# GNSS_FE.net
KiCad netlist of a schematic drawn in Altium Designer
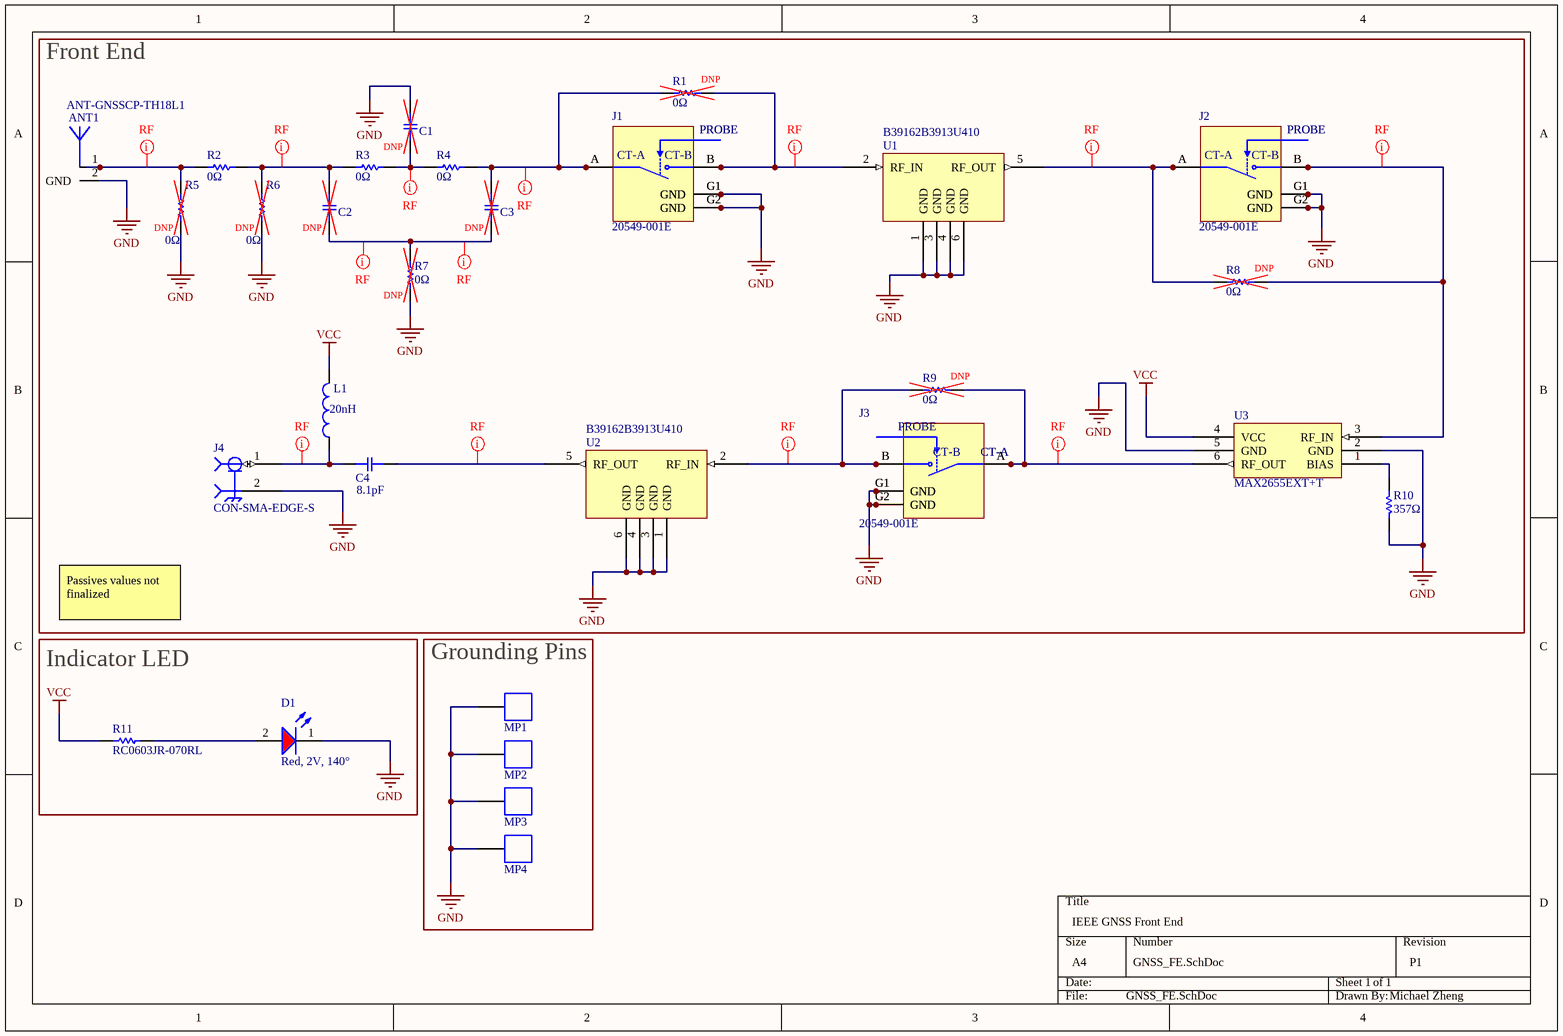
[diagram p0: GNSS_FE.SchDoc]

(export (version "E")
  (design (tool "Eeschema 10.0.6"))
  (components
    (comp (ref "ANT1")
      (value "ANT-GNSSCP-TH18L1")
      (footprint "ANT-GNSSCP-TH18L1")
      (description "CERAMIC PATCH GNSS ANTENNA")
      (libsource (lib "Symbols") (part "ANT-GNSSCP-TH18L1"))
    )
    (comp (ref "C1")
      (value "GRM188R61A105KA61D")
      (footprint "CAP_MURATA_0603")
      (description "CAP CER 1UF 10V X5R 0603")
      (libsource (lib "Symbols") (part "GRM188R61A105KA61D"))
    )
    (comp (ref "C2")
      (value "GRM188R61A105KA61D")
      (footprint "CAP_MURATA_0603")
      (description "CAP CER 1UF 10V X5R 0603")
      (libsource (lib "Symbols") (part "GRM188R61A105KA61D"))
    )
    (comp (ref "C3")
      (value "GRM188R61A105KA61D")
      (footprint "CAP_MURATA_0603")
      (description "CAP CER 1UF 10V X5R 0603")
      (libsource (lib "Symbols") (part "GRM188R61A105KA61D"))
    )
    (comp (ref "C4")
      (value "GRM188R61A105KA61D")
      (footprint "CAP_MURATA_0603")
      (description "CAP CER 1UF 10V X5R 0603")
      (fields (field (name "CAPACITANCE") "8.1pF"))
      (libsource (lib "Symbols") (part "GRM188R61A105KA61D"))
    )
    (comp (ref "D1")
      (value "Red, 2V, 140°")
      (footprint "WL-SMCW")
      (description "WL-SMCW Mono-color Chip LED Waterclear, SMT, size 0603, Red, 2V, 140°")
      (fields
        (field (name "MANUFACTURER PART NUMBER") "150060RS75000")
        (field (name "MANUFACTURER") "Wurth Elektronik")
      )
      (libsource (lib "Symbols") (part "150060RS75000"))
    )
    (comp (ref "J1")
      (value "20549-001E")
      (footprint "footprints:IPEX_20549-001E")
      (fields (field (name "MF") "I-PEX"))
      (libsource (lib "Symbols") (part "20549-001E"))
    )
    (comp (ref "J2")
      (value "20549-001E")
      (footprint "footprints:IPEX_20549-001E")
      (fields (field (name "MF") "I-PEX"))
      (libsource (lib "Symbols") (part "20549-001E"))
    )
    (comp (ref "J3")
      (value "20549-001E")
      (footprint "footprints:IPEX_20549-001E")
      (fields (field (name "MF") "I-PEX"))
      (libsource (lib "") (part "20549-001E_1"))
    )
    (comp (ref "J4")
      (value "CON-SMA-EDGE-S")
      (footprint "RFSOLUTIONS_CON-SMA-EDGE-S")
      (description "CONN SMA JACK STR EDGE MNT")
      (libsource (lib "Symbols") (part "CON-SMA-EDGE-S"))
    )
    (comp (ref "L1")
      (value "20nH")
      (footprint "INDC1006X60N")
      (description "FIXED IND 3.6NH 900MA 40 MOHM")
      (fields (field (name "MP") "LQW15AN3N6C10D"))
      (libsource (lib "Symbols") (part "LQW15AN3N6C10D"))
    )
    (comp (ref "MP1")
      (value "36900000")
      (footprint "36900000")
      (description "WE-SHC Shielding Cabinet, Clip, Tin Plated, Tape and Reel, 6.5x0.8x1.27mm")
      (fields (field (name "MANUFACTURER") "Wurth Elektronik"))
      (libsource (lib "Symbols") (part "36900000"))
    )
    (comp (ref "MP2")
      (value "36900000")
      (footprint "36900000")
      (description "WE-SHC Shielding Cabinet, Clip, Tin Plated, Tape and Reel, 6.5x0.8x1.27mm")
      (fields (field (name "MANUFACTURER") "Wurth Elektronik"))
      (libsource (lib "Symbols") (part "36900000"))
    )
    (comp (ref "MP3")
      (value "36900000")
      (footprint "36900000")
      (description "WE-SHC Shielding Cabinet, Clip, Tin Plated, Tape and Reel, 6.5x0.8x1.27mm")
      (fields (field (name "MANUFACTURER") "Wurth Elektronik"))
      (libsource (lib "Symbols") (part "36900000"))
    )
    (comp (ref "MP4")
      (value "36900000")
      (footprint "36900000")
      (description "WE-SHC Shielding Cabinet, Clip, Tin Plated, Tape and Reel, 6.5x0.8x1.27mm")
      (fields (field (name "MANUFACTURER") "Wurth Elektronik"))
      (libsource (lib "Symbols") (part "36900000"))
    )
    (comp (ref "R1")
      (value "RC0603JR-070RL")
      (footprint "RC0603JR-070RL")
      (description "Chip Resistor, 0 Ohm, +/- 5%, 0.1 W, -55 to 155 degC, 0603 (1608 Metric), RoHS, Tape and Reel")
      (fields
        (field (name "TOLERANCE") "5%")
        (field (name "RESISTANCE") "0Ω")
        (field (name "MANUFACTURER") "Yageo")
      )
      (libsource (lib "Symbols") (part "RC0603JR-070RL"))
    )
    (comp (ref "R2")
      (value "RC0603JR-070RL")
      (footprint "RC0603JR-070RL")
      (description "Chip Resistor, 0 Ohm, +/- 5%, 0.1 W, -55 to 155 degC, 0603 (1608 Metric), RoHS, Tape and Reel")
      (fields
        (field (name "TOLERANCE") "5%")
        (field (name "RESISTANCE") "0Ω")
        (field (name "MANUFACTURER") "Yageo")
      )
      (libsource (lib "Symbols") (part "RC0603JR-070RL"))
    )
    (comp (ref "R3")
      (value "RC0603JR-070RL")
      (footprint "RC0603JR-070RL")
      (description "Chip Resistor, 0 Ohm, +/- 5%, 0.1 W, -55 to 155 degC, 0603 (1608 Metric), RoHS, Tape and Reel")
      (fields
        (field (name "TOLERANCE") "5%")
        (field (name "RESISTANCE") "0Ω")
        (field (name "MANUFACTURER") "Yageo")
      )
      (libsource (lib "Symbols") (part "RC0603JR-070RL"))
    )
    (comp (ref "R4")
      (value "RC0603JR-070RL")
      (footprint "RC0603JR-070RL")
      (description "Chip Resistor, 0 Ohm, +/- 5%, 0.1 W, -55 to 155 degC, 0603 (1608 Metric), RoHS, Tape and Reel")
      (fields
        (field (name "TOLERANCE") "5%")
        (field (name "RESISTANCE") "0Ω")
        (field (name "MANUFACTURER") "Yageo")
      )
      (libsource (lib "Symbols") (part "RC0603JR-070RL"))
    )
    (comp (ref "R5")
      (value "RC0603JR-070RL")
      (footprint "RC0603JR-070RL")
      (description "Chip Resistor, 0 Ohm, +/- 5%, 0.1 W, -55 to 155 degC, 0603 (1608 Metric), RoHS, Tape and Reel")
      (fields
        (field (name "TOLERANCE") "5%")
        (field (name "RESISTANCE") "0Ω")
        (field (name "MANUFACTURER") "Yageo")
      )
      (libsource (lib "Symbols") (part "RC0603JR-070RL"))
    )
    (comp (ref "R6")
      (value "RC0603JR-070RL")
      (footprint "RC0603JR-070RL")
      (description "Chip Resistor, 0 Ohm, +/- 5%, 0.1 W, -55 to 155 degC, 0603 (1608 Metric), RoHS, Tape and Reel")
      (fields
        (field (name "TOLERANCE") "5%")
        (field (name "RESISTANCE") "0Ω")
        (field (name "MANUFACTURER") "Yageo")
      )
      (libsource (lib "Symbols") (part "RC0603JR-070RL"))
    )
    (comp (ref "R7")
      (value "RC0603JR-070RL")
      (footprint "RC0603JR-070RL")
      (description "Chip Resistor, 0 Ohm, +/- 5%, 0.1 W, -55 to 155 degC, 0603 (1608 Metric), RoHS, Tape and Reel")
      (fields
        (field (name "TOLERANCE") "5%")
        (field (name "RESISTANCE") "0Ω")
        (field (name "MANUFACTURER") "Yageo")
      )
      (libsource (lib "Symbols") (part "RC0603JR-070RL"))
    )
    (comp (ref "R8")
      (value "RC0603JR-070RL")
      (footprint "RC0603JR-070RL")
      (description "Chip Resistor, 0 Ohm, +/- 5%, 0.1 W, -55 to 155 degC, 0603 (1608 Metric), RoHS, Tape and Reel")
      (fields
        (field (name "TOLERANCE") "5%")
        (field (name "RESISTANCE") "0Ω")
        (field (name "MANUFACTURER") "Yageo")
      )
      (libsource (lib "Symbols") (part "RC0603JR-070RL"))
    )
    (comp (ref "R9")
      (value "RC0603JR-070RL")
      (footprint "RC0603JR-070RL")
      (description "Chip Resistor, 0 Ohm, +/- 5%, 0.1 W, -55 to 155 degC, 0603 (1608 Metric), RoHS, Tape and Reel")
      (fields
        (field (name "TOLERANCE") "5%")
        (field (name "RESISTANCE") "0Ω")
        (field (name "MANUFACTURER") "Yageo")
      )
      (libsource (lib "Symbols") (part "RC0603JR-070RL"))
    )
    (comp (ref "R10")
      (value "~")
      (footprint "RC0603JR-070RL")
      (description "Chip Resistor, 0 Ohm, +/- 5%, 0.1 W, -55 to 155 degC, 0603 (1608 Metric), RoHS, Tape and Reel")
      (fields
        (field (name "TOLERANCE") "5%")
        (field (name "RESISTANCE") "357Ω")
        (field (name "MANUFACTURER") "Yageo")
      )
      (libsource (lib "Symbols") (part "RC0603JR-070RL"))
    )
    (comp (ref "R11")
      (value "RC0603JR-070RL")
      (footprint "RC0603JR-070RL")
      (description "Chip Resistor, 0 Ohm, +/- 5%, 0.1 W, -55 to 155 degC, 0603 (1608 Metric), RoHS, Tape and Reel")
      (fields (field (name "TOLERANCE") "5%") (field (name "MANUFACTURER") "Yageo"))
      (libsource (lib "Symbols") (part "RC0603JR-070RL"))
    )
    (comp (ref "U1")
      (value "B39162B3913U410")
      (footprint "B39162B3913U410")
      (description "FILTER SAW 1.588GHZ 6SMD")
      (libsource (lib "Symbols") (part "B39162B3913U410"))
    )
    (comp (ref "U2")
      (value "B39162B3913U410")
      (footprint "B39162B3913U410")
      (description "FILTER SAW 1.588GHZ 6SMD")
      (libsource (lib "") (part "B39162B3913U410_1"))
    )
    (comp (ref "U3")
      (value "MAX2655EXT+T")
      (footprint "MAX2655EXT+T")
      (description "IC AMP GPS 1.4GHZ-1.7GHZ SC70-6")
      (libsource (lib "Symbols") (part "MAX2655EXT+T"))
    )
  )
  (nets
    (net (code "1") (name "GND") (class "Default")
      (node (ref "ANT1") (pin "2") (pinfunction "GND_2") (pintype "passive"))
      (node (ref "C1") (pin "2") (pinfunction "2_2") (pintype "passive"))
      (node (ref "D1") (pin "1") (pinfunction "K_1") (pintype "passive"))
      (node (ref "J1") (pin "G1") (pinfunction "GND_G1") (pintype "power_in"))
      (node (ref "J1") (pin "G2") (pinfunction "GND_G2") (pintype "power_in"))
      (node (ref "J2") (pin "G1") (pinfunction "GND_G1") (pintype "power_in"))
      (node (ref "J2") (pin "G2") (pinfunction "GND_G2") (pintype "power_in"))
      (node (ref "J3") (pin "G1") (pinfunction "GND_G1") (pintype "power_in"))
      (node (ref "J3") (pin "G2") (pinfunction "GND_G2") (pintype "power_in"))
      (node (ref "J4") (pin "2") (pinfunction "GND_2") (pintype "power_in"))
      (node (ref "MP1") (pin "1") (pinfunction "1_1") (pintype "passive"))
      (node (ref "MP2") (pin "1") (pinfunction "1_1") (pintype "passive"))
      (node (ref "MP3") (pin "1") (pinfunction "1_1") (pintype "passive"))
      (node (ref "MP4") (pin "1") (pinfunction "1_1") (pintype "passive"))
      (node (ref "R10") (pin "2") (pinfunction "2_2") (pintype "passive"))
      (node (ref "R5") (pin "1") (pinfunction "1_1") (pintype "passive"))
      (node (ref "R6") (pin "1") (pinfunction "1_1") (pintype "passive"))
      (node (ref "R7") (pin "2") (pinfunction "2_2") (pintype "passive"))
      (node (ref "U1") (pin "1") (pinfunction "GND_1") (pintype "power_in"))
      (node (ref "U1") (pin "3") (pinfunction "GND_3") (pintype "power_in"))
      (node (ref "U1") (pin "4") (pinfunction "GND_4") (pintype "power_in"))
      (node (ref "U1") (pin "6") (pinfunction "GND_6") (pintype "power_in"))
      (node (ref "U2") (pin "1") (pinfunction "GND_1") (pintype "power_in"))
      (node (ref "U2") (pin "3") (pinfunction "GND_3") (pintype "power_in"))
      (node (ref "U2") (pin "4") (pinfunction "GND_4") (pintype "power_in"))
      (node (ref "U2") (pin "6") (pinfunction "GND_6") (pintype "power_in"))
      (node (ref "U3") (pin "2") (pinfunction "GND_2") (pintype "power_in"))
      (node (ref "U3") (pin "5") (pinfunction "GND_5") (pintype "power_in"))
    )
    (net (code "2") (name "Net-(ANT1-RF_IN)") (class "Default")
      (node (ref "ANT1") (pin "1") (pinfunction "RF_IN_1") (pintype "passive"))
      (node (ref "R2") (pin "2") (pinfunction "2_2") (pintype "passive"))
      (node (ref "R5") (pin "2") (pinfunction "2_2") (pintype "passive"))
    )
    (net (code "3") (name "Net-(C1-Pad1)") (class "Default")
      (node (ref "C1") (pin "1") (pinfunction "1_1") (pintype "passive"))
      (node (ref "R3") (pin "1") (pinfunction "1_1") (pintype "passive"))
      (node (ref "R4") (pin "2") (pinfunction "2_2") (pintype "passive"))
    )
    (net (code "4") (name "Net-(C2-Pad1)") (class "Default")
      (node (ref "C2") (pin "1") (pinfunction "1_1") (pintype "passive"))
      (node (ref "C3") (pin "1") (pinfunction "1_1") (pintype "passive"))
      (node (ref "R7") (pin "1") (pinfunction "1_1") (pintype "passive"))
    )
    (net (code "5") (name "Net-(C2-Pad2)") (class "Default")
      (node (ref "C2") (pin "2") (pinfunction "2_2") (pintype "passive"))
      (node (ref "R2") (pin "1") (pinfunction "1_1") (pintype "passive"))
      (node (ref "R3") (pin "2") (pinfunction "2_2") (pintype "passive"))
      (node (ref "R6") (pin "2") (pinfunction "2_2") (pintype "passive"))
    )
    (net (code "6") (name "Net-(D1-A)") (class "Default")
      (node (ref "D1") (pin "2") (pinfunction "A_2") (pintype "passive"))
      (node (ref "R11") (pin "2") (pinfunction "2_2") (pintype "passive"))
    )
    (net (code "7") (name "Net-(J1-CT-A)") (class "Default")
      (node (ref "C3") (pin "2") (pinfunction "2_2") (pintype "passive"))
      (node (ref "J1") (pin "A") (pinfunction "CT-A_A") (pintype "passive"))
      (node (ref "R1") (pin "2") (pinfunction "2_2") (pintype "passive"))
      (node (ref "R4") (pin "1") (pinfunction "1_1") (pintype "passive"))
    )
    (net (code "8") (name "Net-(J1-CT-B)") (class "Default")
      (node (ref "J1") (pin "B") (pinfunction "CT-B_B") (pintype "passive"))
      (node (ref "R1") (pin "1") (pinfunction "1_1") (pintype "passive"))
      (node (ref "U1") (pin "2") (pinfunction "RF_IN_2") (pintype "input"))
    )
    (net (code "9") (name "Net-(J2-CT-A)") (class "Default")
      (node (ref "J2") (pin "A") (pinfunction "CT-A_A") (pintype "passive"))
      (node (ref "R8") (pin "2") (pinfunction "2_2") (pintype "passive"))
      (node (ref "U1") (pin "5") (pinfunction "RF_OUT_5") (pintype "output"))
    )
    (net (code "10") (name "Net-(J2-CT-B)") (class "Default")
      (node (ref "J2") (pin "B") (pinfunction "CT-B_B") (pintype "passive"))
      (node (ref "R8") (pin "1") (pinfunction "1_1") (pintype "passive"))
      (node (ref "U3") (pin "3") (pinfunction "RF_IN_3") (pintype "input"))
    )
    (net (code "11") (name "Net-(J3-CT-A)") (class "Default")
      (node (ref "J3") (pin "A") (pinfunction "CT-A_A") (pintype "passive"))
      (node (ref "R9") (pin "2") (pinfunction "2_2") (pintype "passive"))
      (node (ref "U3") (pin "6") (pinfunction "RF_OUT_6") (pintype "output"))
    )
    (net (code "12") (name "Net-(J3-CT-B)") (class "Default")
      (node (ref "J3") (pin "B") (pinfunction "CT-B_B") (pintype "passive"))
      (node (ref "R9") (pin "1") (pinfunction "1_1") (pintype "passive"))
      (node (ref "U2") (pin "2") (pinfunction "RF_IN_2") (pintype "input"))
    )
    (net (code "13") (name "Net-(J4-RF)") (class "Default")
      (node (ref "C4") (pin "2") (pinfunction "2_2") (pintype "passive"))
      (node (ref "J4") (pin "1") (pinfunction "RF_1") (pintype "bidirectional"))
      (node (ref "L1") (pin "1") (pinfunction "1_1") (pintype "passive"))
    )
    (net (code "14") (name "Net-(U2-RF_OUT)") (class "Default")
      (node (ref "C4") (pin "1") (pinfunction "1_1") (pintype "passive"))
      (node (ref "U2") (pin "5") (pinfunction "RF_OUT_5") (pintype "output"))
    )
    (net (code "15") (name "Net-(U3-BIAS)") (class "Default")
      (node (ref "R10") (pin "1") (pinfunction "1_1") (pintype "passive"))
      (node (ref "U3") (pin "1") (pinfunction "BIAS_1") (pintype "passive"))
    )
    (net (code "16") (name "VCC") (class "Default")
      (node (ref "L1") (pin "2") (pinfunction "2_2") (pintype "passive"))
      (node (ref "R11") (pin "1") (pinfunction "1_1") (pintype "passive"))
      (node (ref "U3") (pin "4") (pinfunction "VCC_4") (pintype "power_in"))
    )
  )
)
